# nerves_key1.net
KiCad netlist of a schematic drawn in EAGLE
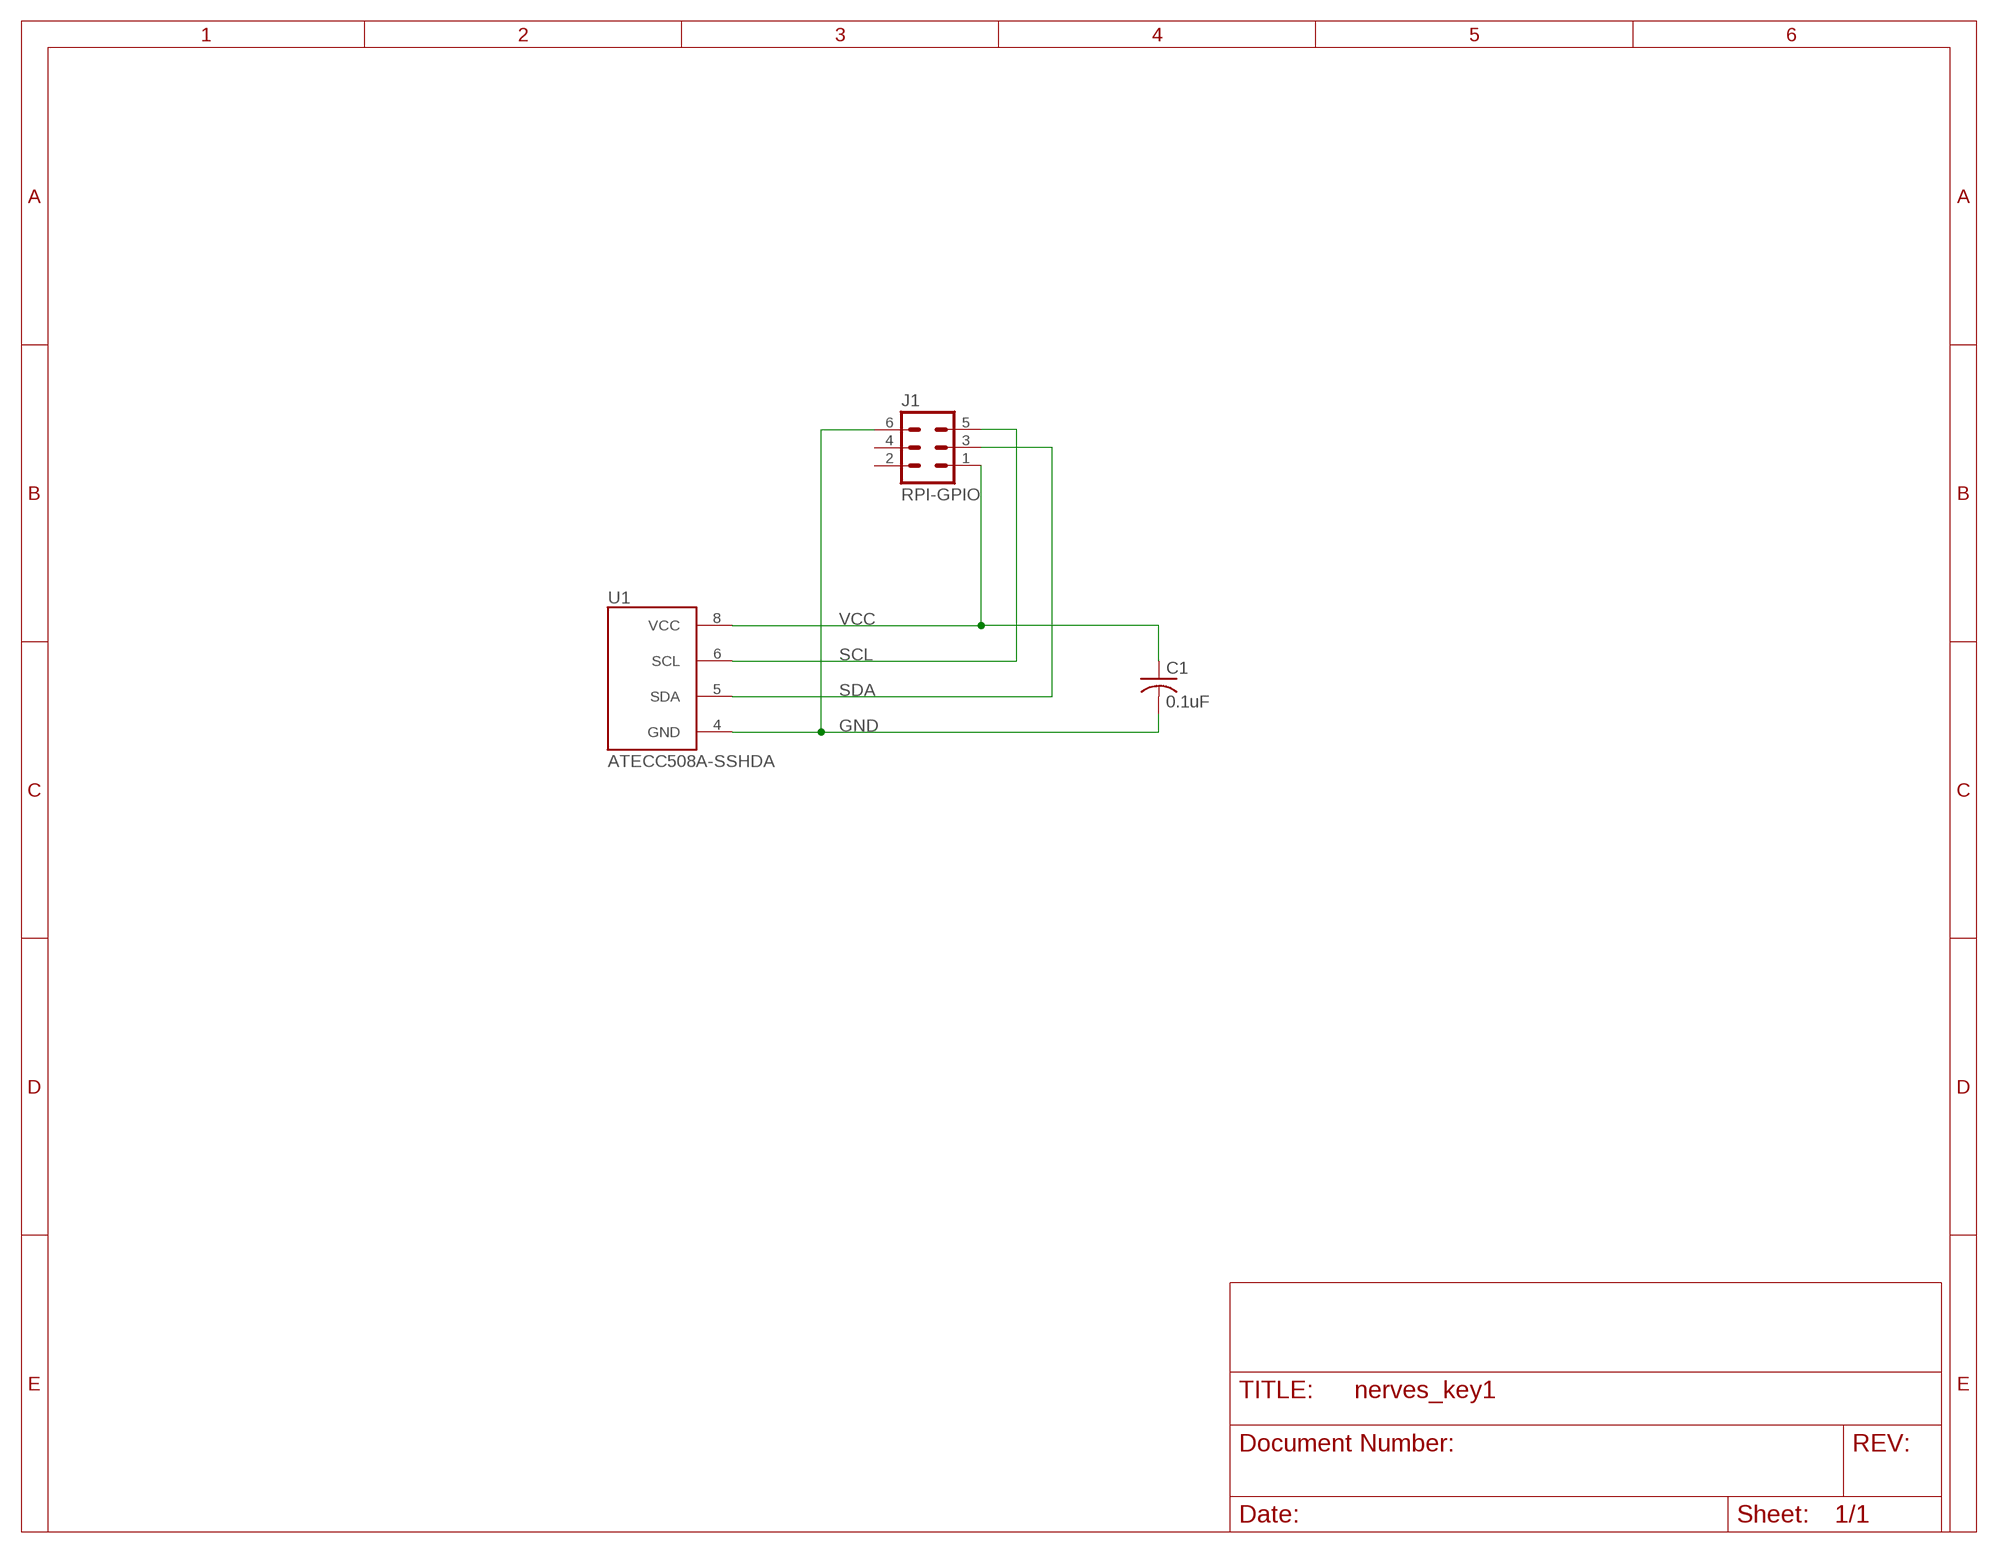
[diagram p0: schematic, sheet 1]

(export (version "E")
  (design (tool "Eeschema 10.0.6"))
  (components
    (comp (ref "C1")
      (value "0.1uF")
      (footprint "eagle-import:C0805")
      (libsource (lib "eagle-import") (part "C-USC0805"))
    )
    (comp (ref "J1")
      (value "RPI-GPIO")
      (footprint "eagle-import:MA03-2")
      (libsource (lib "eagle-import") (part "MA03-2"))
    )
    (comp (ref "U1")
      (value "ATECC508A-SSHDA")
      (footprint "eagle-import:SOIC127P625X175-8")
      (libsource (lib "eagle-import") (part "ATECC508ASOIC-8-NARROW"))
    )
  )
  (nets
    (net (code "1") (name "/GND") (class "Default")
      (node (ref "C1") (pin "2") (pinfunction "2_2") (pintype "passive"))
      (node (ref "J1") (pin "6") (pinfunction "6_6") (pintype "passive"))
      (node (ref "U1") (pin "4") (pinfunction "GND_4") (pintype "bidirectional"))
    )
    (net (code "2") (name "/SCL") (class "Default")
      (node (ref "J1") (pin "5") (pinfunction "5_5") (pintype "passive"))
      (node (ref "U1") (pin "6") (pinfunction "SCL_6") (pintype "bidirectional"))
    )
    (net (code "3") (name "/SDA") (class "Default")
      (node (ref "J1") (pin "3") (pinfunction "3_3") (pintype "passive"))
      (node (ref "U1") (pin "5") (pinfunction "SDA_5") (pintype "bidirectional"))
    )
    (net (code "4") (name "/VCC") (class "Default")
      (node (ref "C1") (pin "1") (pinfunction "1_1") (pintype "passive"))
      (node (ref "J1") (pin "1") (pinfunction "1_1") (pintype "passive"))
      (node (ref "U1") (pin "8") (pinfunction "VCC_8") (pintype "bidirectional"))
    )
    (net (code "5") (name "unconnected-(J1-Pad2)") (class "Default")
      (node (ref "J1") (pin "2") (pinfunction "2_2") (pintype "passive"))
    )
    (net (code "6") (name "unconnected-(J1-Pad4)") (class "Default")
      (node (ref "J1") (pin "4") (pinfunction "4_4") (pintype "passive"))
    )
  )
)
